# DAU_Kupplung_3phasig_V1_13.net
KiCad netlist of a schematic drawn in Altium Designer
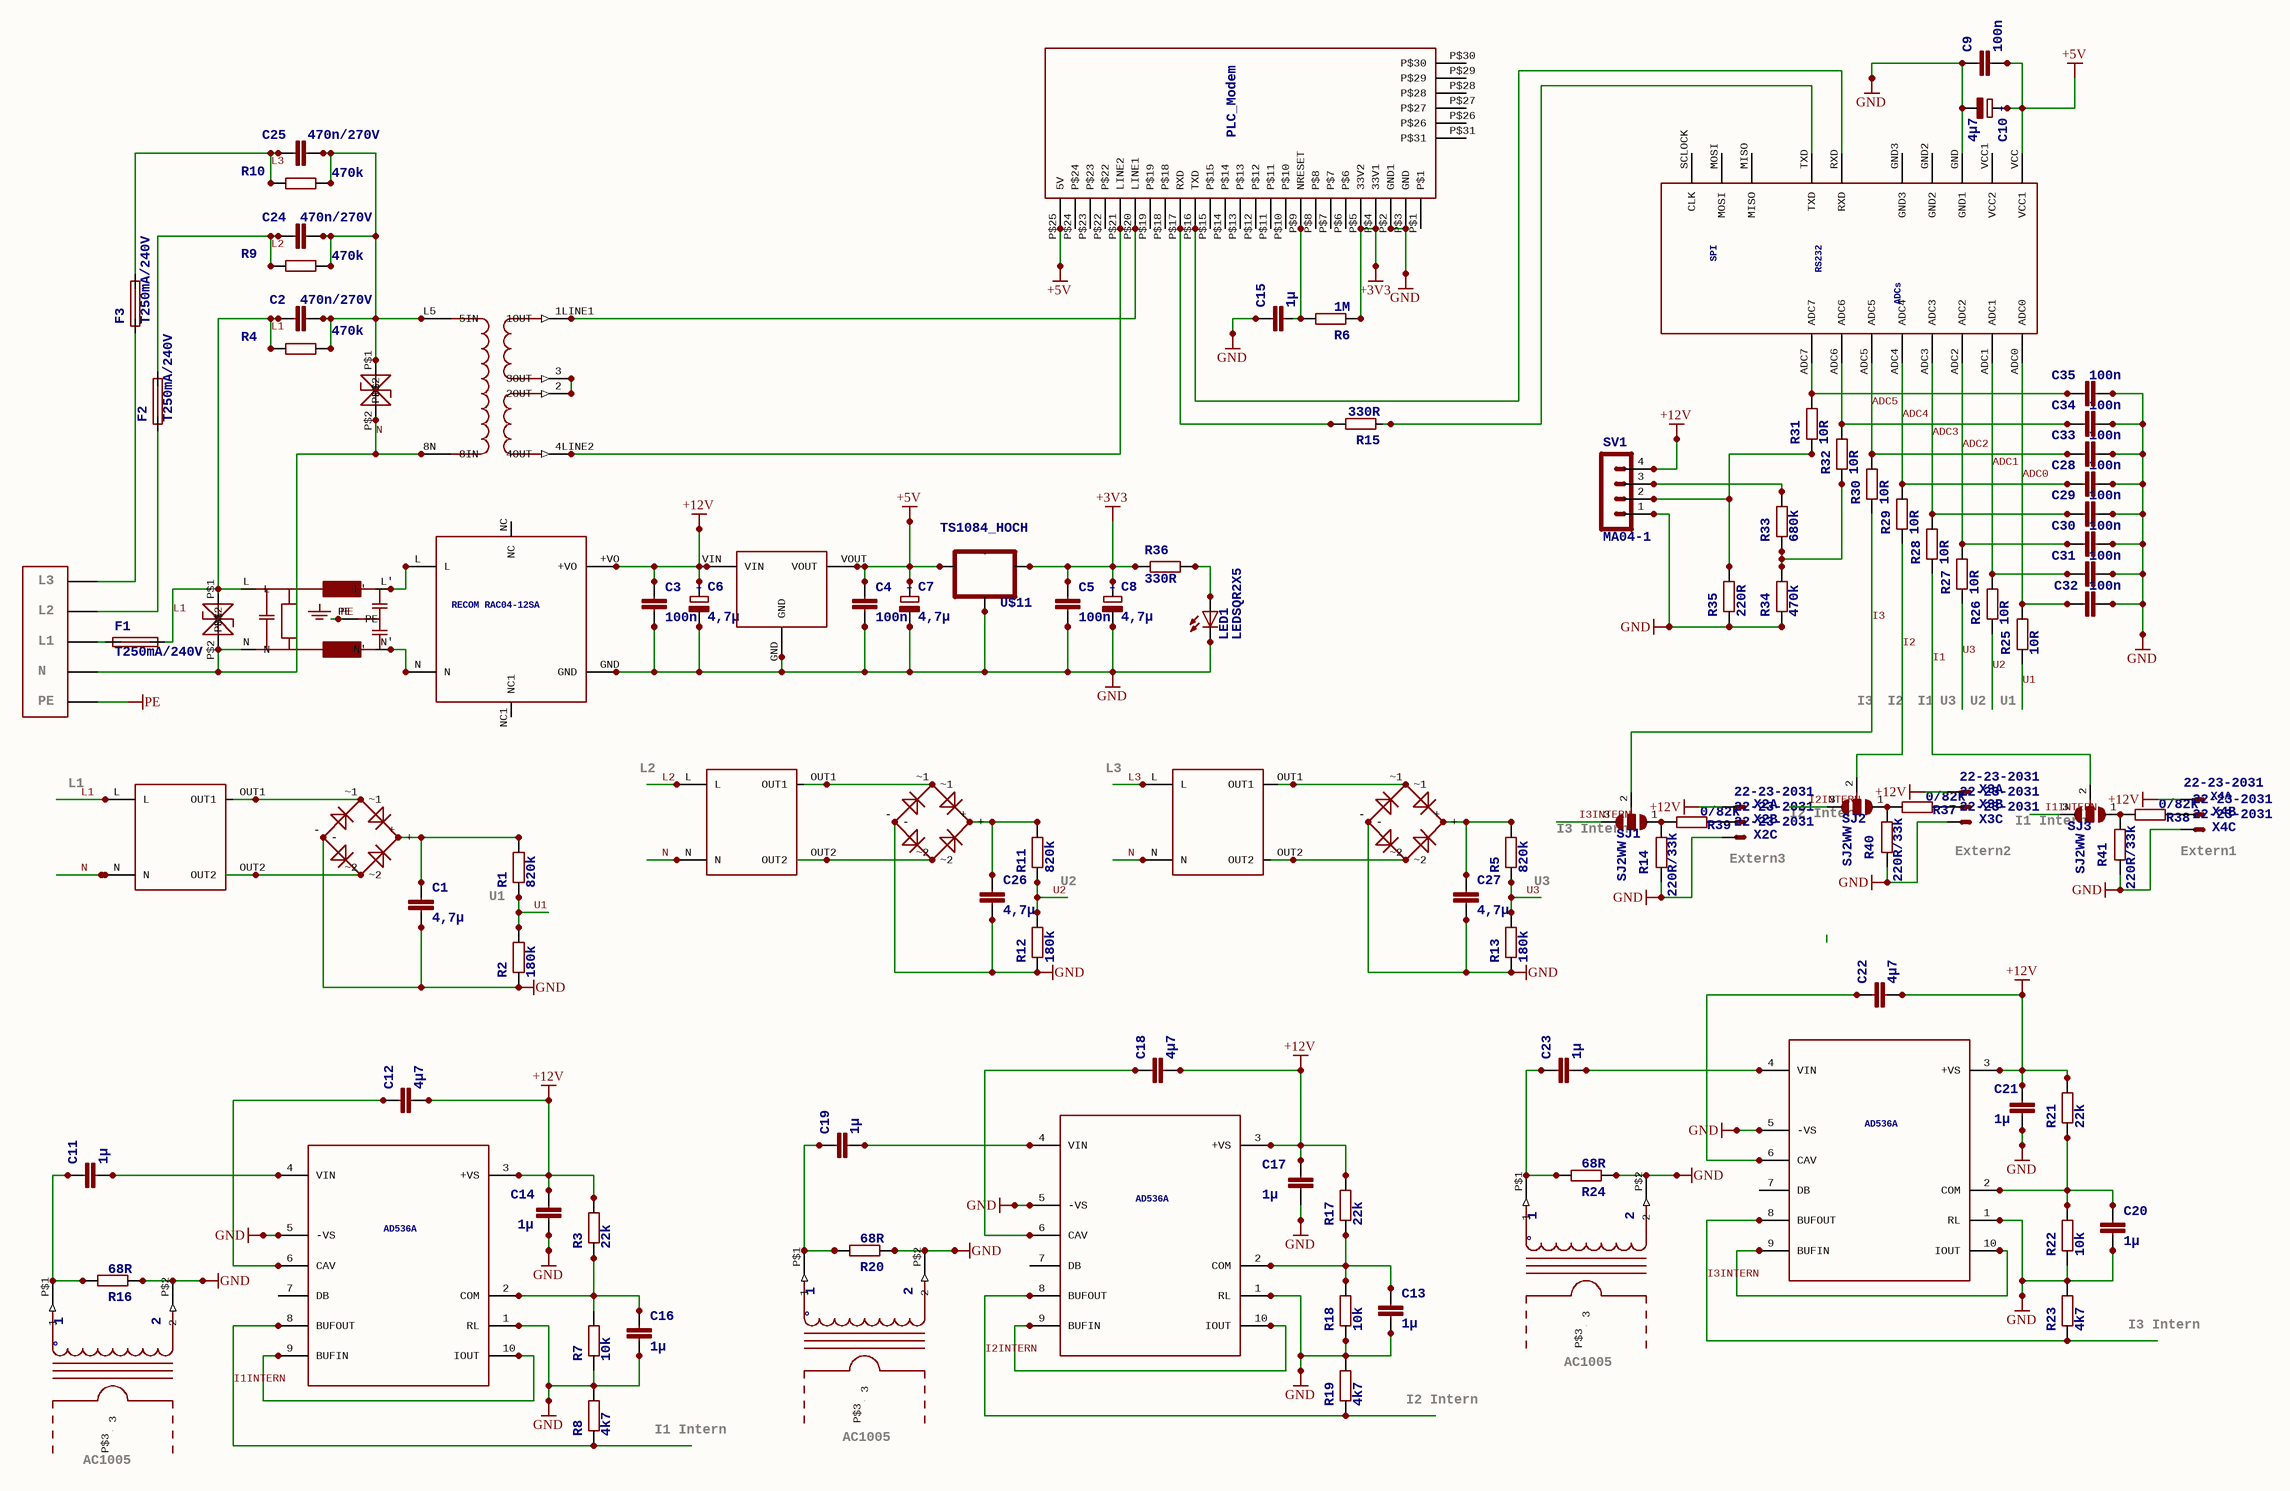
[diagram p0: DAU_Kupplung_3phasig_V1_13.SchDoc]

(export (version "E")
  (design (tool "Eeschema 10.0.6"))
  (components
    (comp (ref "AC1002_1")
      (value "AC1010")
      (footprint "AC1010")
      (fields (field (name "°") "°") (field (name "1") "1") (field (name "2") "2"))
      (libsource (lib "ADS") (part "AC1010"))
    )
    (comp (ref "C1")
      (value "4,7µ")
      (footprint "C1206")
      (description "<B>CAPACITOR</B>, European symbol")
      (libsource (lib "resistor") (part "C-EUC1206"))
    )
    (comp (ref "C2")
      (value "470n/270V")
      (footprint "C225-087X268")
      (description "<B>CAPACITOR</B>, European symbol")
      (libsource (lib "resistor") (part "C-EU225-087X268"))
    )
    (comp (ref "C3")
      (value "100n")
      (footprint "C0805K")
      (description "<B>CAPACITOR</B>, European symbol")
      (libsource (lib "") (part "C-EUC0805K_1"))
    )
    (comp (ref "C4")
      (value "100n")
      (footprint "C0805K")
      (description "<B>CAPACITOR</B>, European symbol")
      (libsource (lib "") (part "C-EUC0805K_1"))
    )
    (comp (ref "C5")
      (value "100n")
      (footprint "C0805K")
      (description "<B>CAPACITOR</B>, European symbol")
      (libsource (lib "") (part "C-EUC0805K_1"))
    )
    (comp (ref "C6")
      (value "4,7µ")
      (footprint "E2,5-6")
      (description "<B>POLARIZED CAPACITOR</B>, European symbol")
      (fields (field (name "+") "+"))
      (libsource (lib "resistor") (part "CPOL-EUE2.5-6"))
    )
    (comp (ref "C7")
      (value "4,7µ")
      (footprint "E2,5-6")
      (description "<B>POLARIZED CAPACITOR</B>, European symbol")
      (fields (field (name "+") "+"))
      (libsource (lib "resistor") (part "CPOL-EUE2.5-6"))
    )
    (comp (ref "C8")
      (value "4,7µ")
      (footprint "E2,5-6")
      (description "<B>POLARIZED CAPACITOR</B>, European symbol")
      (fields (field (name "+") "+"))
      (libsource (lib "resistor") (part "CPOL-EUE2.5-6"))
    )
    (comp (ref "C9")
      (value "100n")
      (footprint "C0805K")
      (description "<B>CAPACITOR</B>, European symbol")
      (libsource (lib "resistor") (part "C-EUC0805K"))
    )
    (comp (ref "C10")
      (value "4µ7")
      (footprint "E2,5-6E")
      (description "<B>POLARIZED CAPACITOR</B>, European symbol")
      (fields (field (name "+") "+"))
      (libsource (lib "rcl") (part "CPOL-EUE2,5-6E"))
    )
    (comp (ref "C11")
      (value "1µ")
      (footprint "C0805K")
      (description "<B>CAPACITOR</B>, European symbol")
      (libsource (lib "resistor") (part "C-EUC0805K"))
    )
    (comp (ref "C12")
      (value "4µ7")
      (footprint "C0805K")
      (description "<B>CAPACITOR</B>, European symbol")
      (libsource (lib "resistor") (part "C-EUC0805K"))
    )
    (comp (ref "C13")
      (value "1µ")
      (footprint "C0805K")
      (description "<B>CAPACITOR</B>, European symbol")
      (libsource (lib "") (part "C-EUC0805K_1"))
    )
    (comp (ref "C14")
      (value "1µ")
      (footprint "C0805K")
      (description "<B>CAPACITOR</B>, European symbol")
      (libsource (lib "") (part "C-EUC0805K_2"))
    )
    (comp (ref "C15")
      (value "1µ")
      (footprint "C0805K")
      (description "<B>CAPACITOR</B>, European symbol")
      (libsource (lib "resistor") (part "C-EUC0805K"))
    )
    (comp (ref "C16")
      (value "1µ")
      (footprint "C0805K")
      (description "<B>CAPACITOR</B>, European symbol")
      (libsource (lib "") (part "C-EUC0805K_1"))
    )
    (comp (ref "C17")
      (value "1µ")
      (footprint "C0805K")
      (description "<B>CAPACITOR</B>, European symbol")
      (libsource (lib "") (part "C-EUC0805K_2"))
    )
    (comp (ref "C18")
      (value "4µ7")
      (footprint "C0805K")
      (description "<B>CAPACITOR</B>, European symbol")
      (libsource (lib "resistor") (part "C-EUC0805K"))
    )
    (comp (ref "C19")
      (value "1µ")
      (footprint "C0805K")
      (description "<B>CAPACITOR</B>, European symbol")
      (libsource (lib "resistor") (part "C-EUC0805K"))
    )
    (comp (ref "C20")
      (value "1µ")
      (footprint "C0805K")
      (description "<B>CAPACITOR</B>, European symbol")
      (libsource (lib "") (part "C-EUC0805K_1"))
    )
    (comp (ref "C21")
      (value "1µ")
      (footprint "C0805K")
      (description "<B>CAPACITOR</B>, European symbol")
      (libsource (lib "") (part "C-EUC0805K_1"))
    )
    (comp (ref "C22")
      (value "4µ7")
      (footprint "C0805K")
      (description "<B>CAPACITOR</B>, European symbol")
      (libsource (lib "resistor") (part "C-EUC0805K"))
    )
    (comp (ref "C23")
      (value "1µ")
      (footprint "C0805K")
      (description "<B>CAPACITOR</B>, European symbol")
      (libsource (lib "resistor") (part "C-EUC0805K"))
    )
    (comp (ref "C24")
      (value "470n/270V")
      (footprint "C225-087X268")
      (description "<B>CAPACITOR</B>, European symbol")
      (libsource (lib "resistor") (part "C-EU225-087X268"))
    )
    (comp (ref "C25")
      (value "470n/270V")
      (footprint "C225-087X268")
      (description "<B>CAPACITOR</B>, European symbol")
      (libsource (lib "resistor") (part "C-EU225-087X268"))
    )
    (comp (ref "C26")
      (value "4,7µ")
      (footprint "C1206")
      (description "<B>CAPACITOR</B>, European symbol")
      (libsource (lib "resistor") (part "C-EUC1206"))
    )
    (comp (ref "C27")
      (value "4,7µ")
      (footprint "C1206")
      (description "<B>CAPACITOR</B>, European symbol")
      (libsource (lib "resistor") (part "C-EUC1206"))
    )
    (comp (ref "C28")
      (value "100n")
      (footprint "C0805K")
      (description "<B>CAPACITOR</B>, European symbol")
      (libsource (lib "resistor") (part "C-EUC0805K"))
    )
    (comp (ref "C29")
      (value "100n")
      (footprint "C0805K")
      (description "<B>CAPACITOR</B>, European symbol")
      (libsource (lib "resistor") (part "C-EUC0805K"))
    )
    (comp (ref "C30")
      (value "100n")
      (footprint "C0805K")
      (description "<B>CAPACITOR</B>, European symbol")
      (libsource (lib "resistor") (part "C-EUC0805K"))
    )
    (comp (ref "C31")
      (value "100n")
      (footprint "C0805K")
      (description "<B>CAPACITOR</B>, European symbol")
      (libsource (lib "resistor") (part "C-EUC0805K"))
    )
    (comp (ref "C32")
      (value "100n")
      (footprint "C0805K")
      (description "<B>CAPACITOR</B>, European symbol")
      (libsource (lib "resistor") (part "C-EUC0805K"))
    )
    (comp (ref "C33")
      (value "100n")
      (footprint "C0805K")
      (description "<B>CAPACITOR</B>, European symbol")
      (libsource (lib "resistor") (part "C-EUC0805K"))
    )
    (comp (ref "C34")
      (value "100n")
      (footprint "C0805K")
      (description "<B>CAPACITOR</B>, European symbol")
      (libsource (lib "resistor") (part "C-EUC0805K"))
    )
    (comp (ref "C35")
      (value "100n")
      (footprint "C0805K")
      (description "<B>CAPACITOR</B>, European symbol")
      (libsource (lib "resistor") (part "C-EUC0805K"))
    )
    (comp (ref "F1")
      (value "T250mA/240V")
      (footprint "TR5")
      (description "<b>FUSE</b><p>\nWickmann")
      (libsource (lib "fuse") (part "TR5"))
    )
    (comp (ref "F2")
      (value "T250mA/240V")
      (footprint "TR5")
      (description "<b>FUSE</b><p>\nWickmann")
      (libsource (lib "fuse") (part "TR5"))
    )
    (comp (ref "F3")
      (value "T250mA/240V")
      (footprint "TR5")
      (description "<b>FUSE</b><p>\nWickmann")
      (libsource (lib "fuse") (part "TR5"))
    )
    (comp (ref "LED1") (value "LEDSQR2X5") (footprint "LED2X5") (libsource (lib "led") (part "LEDSQR2X5")))
    (comp (ref "P6KE300CA") (value "P6KE300CA") (footprint "TSV") (libsource (lib "ADS") (part "TSV")))
    (comp (ref "R1")
      (value "820k")
      (footprint "R0805")
      (description "<B>RESISTOR</B>, European symbol")
      (libsource (lib "resistor") (part "R-EU_R0805"))
    )
    (comp (ref "R2")
      (value "180k")
      (footprint "R0805")
      (description "<B>RESISTOR</B>, European symbol")
      (libsource (lib "resistor") (part "R-EU_R0805"))
    )
    (comp (ref "R3")
      (value "22k")
      (footprint "R0805")
      (description "<B>RESISTOR</B>, European symbol")
      (libsource (lib "resistor") (part "R-EU_R0805"))
    )
    (comp (ref "R4")
      (value "470k")
      (footprint "0204/7")
      (description "<B>RESISTOR</B>, European symbol")
      (libsource (lib "resistor") (part "R-EU_0204/7"))
    )
    (comp (ref "R5")
      (value "820k")
      (footprint "R0805")
      (description "<B>RESISTOR</B>, European symbol")
      (libsource (lib "resistor") (part "R-EU_R0805"))
    )
    (comp (ref "R6")
      (value "1M")
      (footprint "R0805")
      (description "<B>RESISTOR</B>, European symbol")
      (libsource (lib "resistor") (part "R-EU_R0805"))
    )
    (comp (ref "R7")
      (value "10k")
      (footprint "R0805")
      (description "<B>RESISTOR</B>, European symbol")
      (libsource (lib "resistor") (part "R-EU_R0805"))
    )
    (comp (ref "R8")
      (value "4k7")
      (footprint "R0805")
      (description "<B>RESISTOR</B>, European symbol")
      (libsource (lib "resistor") (part "R-EU_R0805"))
    )
    (comp (ref "R9")
      (value "470k")
      (footprint "0204/7")
      (description "<B>RESISTOR</B>, European symbol")
      (libsource (lib "resistor") (part "R-EU_0204/7"))
    )
    (comp (ref "R10")
      (value "470k")
      (footprint "0204/7")
      (description "<B>RESISTOR</B>, European symbol")
      (libsource (lib "resistor") (part "R-EU_0204/7"))
    )
    (comp (ref "R11")
      (value "820k")
      (footprint "R0805")
      (description "<B>RESISTOR</B>, European symbol")
      (libsource (lib "resistor") (part "R-EU_R0805"))
    )
    (comp (ref "R12")
      (value "180k")
      (footprint "R0805")
      (description "<B>RESISTOR</B>, European symbol")
      (libsource (lib "resistor") (part "R-EU_R0805"))
    )
    (comp (ref "R13")
      (value "180k")
      (footprint "R0805")
      (description "<B>RESISTOR</B>, European symbol")
      (libsource (lib "resistor") (part "R-EU_R0805"))
    )
    (comp (ref "R14")
      (value "220R/33k")
      (footprint "R0805")
      (description "<B>RESISTOR</B>, European symbol")
      (libsource (lib "resistor") (part "R-EU_R0805"))
    )
    (comp (ref "R15")
      (value "330R")
      (footprint "R0805")
      (description "<B>RESISTOR</B>, European symbol")
      (libsource (lib "resistor") (part "R-EU_R0805"))
    )
    (comp (ref "R16")
      (value "68R")
      (footprint "0204/7")
      (description "<B>RESISTOR</B>, European symbol")
      (libsource (lib "resistor") (part "R-EU_0204/7"))
    )
    (comp (ref "R17")
      (value "22k")
      (footprint "R0805")
      (description "<B>RESISTOR</B>, European symbol")
      (libsource (lib "resistor") (part "R-EU_R0805"))
    )
    (comp (ref "R18")
      (value "10k")
      (footprint "R0805")
      (description "<B>RESISTOR</B>, European symbol")
      (libsource (lib "resistor") (part "R-EU_R0805"))
    )
    (comp (ref "R19")
      (value "4k7")
      (footprint "R0805")
      (description "<B>RESISTOR</B>, European symbol")
      (libsource (lib "resistor") (part "R-EU_R0805"))
    )
    (comp (ref "R20")
      (value "68R")
      (footprint "0204/7")
      (description "<B>RESISTOR</B>, European symbol")
      (libsource (lib "resistor") (part "R-EU_0204/7"))
    )
    (comp (ref "R21")
      (value "22k")
      (footprint "R0805")
      (description "<B>RESISTOR</B>, European symbol")
      (libsource (lib "resistor") (part "R-EU_R0805"))
    )
    (comp (ref "R22")
      (value "10k")
      (footprint "R0805")
      (description "<B>RESISTOR</B>, European symbol")
      (libsource (lib "resistor") (part "R-EU_R0805"))
    )
    (comp (ref "R23")
      (value "4k7")
      (footprint "R0805")
      (description "<B>RESISTOR</B>, European symbol")
      (libsource (lib "resistor") (part "R-EU_R0805"))
    )
    (comp (ref "R24")
      (value "68R")
      (footprint "0204/7")
      (description "<B>RESISTOR</B>, European symbol")
      (libsource (lib "resistor") (part "R-EU_0204/7"))
    )
    (comp (ref "R25")
      (value "10R")
      (footprint "R0805")
      (description "<B>RESISTOR</B>, European symbol")
      (libsource (lib "resistor") (part "R-EU_R0805"))
    )
    (comp (ref "R26")
      (value "10R")
      (footprint "R0805")
      (description "<B>RESISTOR</B>, European symbol")
      (libsource (lib "resistor") (part "R-EU_R0805"))
    )
    (comp (ref "R27")
      (value "10R")
      (footprint "R0805")
      (description "<B>RESISTOR</B>, European symbol")
      (libsource (lib "resistor") (part "R-EU_R0805"))
    )
    (comp (ref "R28")
      (value "10R")
      (footprint "R0805")
      (description "<B>RESISTOR</B>, European symbol")
      (libsource (lib "resistor") (part "R-EU_R0805"))
    )
    (comp (ref "R29")
      (value "10R")
      (footprint "R0805")
      (description "<B>RESISTOR</B>, European symbol")
      (libsource (lib "resistor") (part "R-EU_R0805"))
    )
    (comp (ref "R30")
      (value "10R")
      (footprint "R0805")
      (description "<B>RESISTOR</B>, European symbol")
      (libsource (lib "resistor") (part "R-EU_R0805"))
    )
    (comp (ref "R31")
      (value "10R")
      (footprint "R0805")
      (description "<B>RESISTOR</B>, European symbol")
      (libsource (lib "resistor") (part "R-EU_R0805"))
    )
    (comp (ref "R32")
      (value "10R")
      (footprint "R0805")
      (description "<B>RESISTOR</B>, European symbol")
      (libsource (lib "resistor") (part "R-EU_R0805"))
    )
    (comp (ref "R33")
      (value "680k")
      (footprint "R0805")
      (description "<B>RESISTOR</B>, European symbol")
      (libsource (lib "resistor") (part "R-EU_R0805"))
    )
    (comp (ref "R34")
      (value "470k")
      (footprint "R0805")
      (description "<B>RESISTOR</B>, European symbol")
      (libsource (lib "resistor") (part "R-EU_R0805"))
    )
    (comp (ref "R35")
      (value "220R")
      (footprint "R0805")
      (description "<B>RESISTOR</B>, European symbol")
      (libsource (lib "resistor") (part "R-EU_R0805"))
    )
    (comp (ref "R36")
      (value "330R")
      (footprint "R0805")
      (description "<B>RESISTOR</B>, European symbol")
      (libsource (lib "resistor") (part "R-EU_R0805"))
    )
    (comp (ref "R37")
      (value "0/82k")
      (footprint "R0805")
      (description "<B>RESISTOR</B>, European symbol")
      (libsource (lib "resistor") (part "R-EU_R0805"))
    )
    (comp (ref "R38")
      (value "0/82k")
      (footprint "R0805")
      (description "<B>RESISTOR</B>, European symbol")
      (libsource (lib "resistor") (part "R-EU_R0805"))
    )
    (comp (ref "R39")
      (value "0/82k")
      (footprint "R0805")
      (description "<B>RESISTOR</B>, European symbol")
      (libsource (lib "resistor") (part "R-EU_R0805"))
    )
    (comp (ref "R40")
      (value "220R/33k")
      (footprint "R0805")
      (description "<B>RESISTOR</B>, European symbol")
      (libsource (lib "resistor") (part "R-EU_R0805"))
    )
    (comp (ref "R41")
      (value "220R/33k")
      (footprint "R0805")
      (description "<B>RESISTOR</B>, European symbol")
      (libsource (lib "resistor") (part "R-EU_R0805"))
    )
    (comp (ref "SJ1")
      (value "SJ2WW")
      (footprint "SJ_2W")
      (description "SMD solder <b>JUMPER</b>")
      (libsource (lib "jumper") (part "SJ2WW"))
    )
    (comp (ref "SJ2")
      (value "SJ2WW")
      (footprint "SJ_2W")
      (description "SMD solder <b>JUMPER</b>")
      (libsource (lib "jumper") (part "SJ2WW"))
    )
    (comp (ref "SJ3")
      (value "SJ2WW")
      (footprint "SJ_2W")
      (description "SMD solder <b>JUMPER</b>")
      (libsource (lib "jumper") (part "SJ2WW"))
    )
    (comp (ref "SV1")
      (value "MA04-1")
      (footprint "MA04-1")
      (description "<b>PIN HEADER</b>")
      (libsource (lib "con-lstb") (part "MA04-1"))
    )
    (comp (ref "TSV2") (value "TSV") (footprint "TSV") (libsource (lib "ADS") (part "TSV")))
    (comp (ref "U$1")
      (value "RECOM_RAC04_12SA")
      (footprint "RAC04_12SA")
      (fields (field (name "RECOM RAC04-12SA") "RECOM RAC04-12SA"))
      (libsource (lib "ADS") (part "RECOM_RAC04_12SA"))
    )
    (comp (ref "U$2")
      (value "SICHERHEITSTRAFO")
      (footprint "TRAFO_0,35VA")
      (libsource (lib "ADS") (part "SICHERHEITSTRAFO"))
    )
    (comp (ref "U$3")
      (value "ADUC831_MINIMUM")
      (footprint "ADUC_MINIMUM")
      (fields (field (name "SPI") "SPI") (field (name "RS232") "RS232") (field (name "ADCS") "ADCs"))
      (libsource (lib "ADS_ADUCBoards") (part "ADUC831_MINIMUM"))
    )
    (comp (ref "U$4")
      (value "MODEMSTECKER")
      (footprint "MODEM_FUSS")
      (fields (field (name "PLC_MODEM") "PLC_Modem"))
      (libsource (lib "ADS") (part "MODEMSTECKER"))
    )
    (comp (ref "U$5")
      (value "PLC_UEBERTRAGER_V2")
      (footprint "PLC-UEBERTRAGER_V2")
      (libsource (lib "ADS1") (part "PLC_UEBERTRAGER_V2"))
    )
    (comp (ref "U$7")
      (value "AC1010")
      (footprint "AC1010")
      (fields (field (name "°") "°") (field (name "1") "1") (field (name "2") "2"))
      (libsource (lib "ADS") (part "AC1010"))
    )
    (comp (ref "U$8") (value "RECTIFIER") (footprint "RECTIFIER") (libsource (lib "ADS") (part "RECTIFIER")))
    (comp (ref "U$10")
      (value "RECOM_785_05")
      (footprint "RECOM785X")
      (libsource (lib "ADS") (part "RECOM_785_05"))
    )
    (comp (ref "U$11")
      (value "TS1084_HOCH")
      (footprint "TS1084_HOCH")
      (libsource (lib "ADS") (part "TS1084_HOCH"))
    )
    (comp (ref "U$12")
      (value "AD536")
      (footprint "TO100_10PIN")
      (fields (field (name "AD536A") "AD536A"))
      (libsource (lib "ADS") (part "AD536"))
    )
    (comp (ref "U$13")
      (value "AD536")
      (footprint "TO100_10PIN")
      (fields (field (name "AD536A") "AD536A"))
      (libsource (lib "ADS") (part "AD536"))
    )
    (comp (ref "U$14")
      (value "AC1010")
      (footprint "AC1010")
      (fields (field (name "°") "°") (field (name "1") "1") (field (name "2") "2"))
      (libsource (lib "ADS") (part "AC1010"))
    )
    (comp (ref "U$15")
      (value "AD536")
      (footprint "TO100_10PIN")
      (fields (field (name "AD536A") "AD536A"))
      (libsource (lib "ADS") (part "AD536"))
    )
    (comp (ref "U$16")
      (value "SICHERHEITSTRAFO")
      (footprint "TRAFO_0,35VA")
      (libsource (lib "ADS") (part "SICHERHEITSTRAFO"))
    )
    (comp (ref "U$17") (value "RECTIFIER") (footprint "RECTIFIER") (libsource (lib "ADS") (part "RECTIFIER")))
    (comp (ref "U$18")
      (value "SICHERHEITSTRAFO")
      (footprint "TRAFO_0,35VA")
      (libsource (lib "ADS") (part "SICHERHEITSTRAFO"))
    )
    (comp (ref "U$19") (value "RECTIFIER") (footprint "RECTIFIER") (libsource (lib "ADS") (part "RECTIFIER")))
    (comp (ref "U$20")
      (value "NETZFILTER_05_A")
      (footprint "NETZFILTER")
      (libsource (lib "ADS") (part "NETZFILTER_05_A"))
    )
    (comp (ref "X1")
      (value "CONNECTO_5_POL")
      (footprint "CONNECTOR_5_POL")
      (libsource (lib "ADS") (part "CONNECTO_5_POL"))
    )
    (comp (ref "X2")
      (value "22-23-2031")
      (footprint "22-23-2031")
      (description ".100\" (2.54mm) Center Header - 3 Pin")
      (fields (field (name "MF") "MOLEX"))
      (libsource (lib "con-molex") (part "22-23-2031"))
    )
    (comp (ref "X3")
      (value "22-23-2031")
      (footprint "22-23-2031")
      (description ".100\" (2.54mm) Center Header - 3 Pin")
      (fields (field (name "MF") "MOLEX"))
      (libsource (lib "con-molex") (part "22-23-2031"))
    )
    (comp (ref "X4")
      (value "22-23-2031")
      (footprint "22-23-2031")
      (description ".100\" (2.54mm) Center Header - 3 Pin")
      (fields (field (name "MF") "MOLEX"))
      (libsource (lib "con-molex") (part "22-23-2031"))
    )
  )
  (nets
    (net (code "1") (name "+3V3") (class "Default")
      (node (ref "C5") (pin "1") (pinfunction "1_1") (pintype "passive"))
      (node (ref "C8") (pin "+") (pinfunction "+_+") (pintype "passive"))
      (node (ref "R36") (pin "1") (pinfunction "1_1") (pintype "passive"))
      (node (ref "R6") (pin "1") (pinfunction "1_1") (pintype "passive"))
      (node (ref "U$11") (pin "OUT") (pinfunction "OUT_OUT") (pintype "passive"))
      (node (ref "U$4") (pin "P$4") (pinfunction "33V1_P$4") (pintype "passive"))
      (node (ref "U$4") (pin "P$5") (pinfunction "33V2_P$5") (pintype "passive"))
    )
    (net (code "2") (name "+5V") (class "Default")
      (node (ref "C10") (pin "+") (pinfunction "+_+") (pintype "passive"))
      (node (ref "C4") (pin "1") (pinfunction "1_1") (pintype "passive"))
      (node (ref "C7") (pin "+") (pinfunction "+_+") (pintype "passive"))
      (node (ref "C9") (pin "2") (pinfunction "2_2") (pintype "passive"))
      (node (ref "U$10") (pin "VOUT") (pinfunction "VOUT_VOUT") (pintype "passive"))
      (node (ref "U$11") (pin "IN") (pinfunction "IN_IN") (pintype "passive"))
      (node (ref "U$3") (pin "VCC") (pinfunction "VCC1_VCC") (pintype "passive"))
      (node (ref "U$4") (pin "P$25") (pinfunction "5V_P$25") (pintype "passive"))
    )
    (net (code "3") (name "+12V") (class "Default")
      (node (ref "C12") (pin "2") (pinfunction "2_2") (pintype "passive"))
      (node (ref "C14") (pin "2") (pinfunction "2_2") (pintype "passive"))
      (node (ref "C17") (pin "2") (pinfunction "2_2") (pintype "passive"))
      (node (ref "C18") (pin "2") (pinfunction "2_2") (pintype "passive"))
      (node (ref "C21") (pin "1") (pinfunction "1_1") (pintype "passive"))
      (node (ref "C22") (pin "2") (pinfunction "2_2") (pintype "passive"))
      (node (ref "C3") (pin "1") (pinfunction "1_1") (pintype "passive"))
      (node (ref "C6") (pin "+") (pinfunction "+_+") (pintype "passive"))
      (node (ref "R17") (pin "2") (pinfunction "2_2") (pintype "passive"))
      (node (ref "R21") (pin "2") (pinfunction "2_2") (pintype "passive"))
      (node (ref "R3") (pin "2") (pinfunction "2_2") (pintype "passive"))
      (node (ref "SV1") (pin "4") (pinfunction "4_4") (pintype "passive"))
      (node (ref "U$1") (pin "+VO") (pinfunction "+VO_+VO") (pintype "passive"))
      (node (ref "U$10") (pin "VIN") (pinfunction "VIN_VIN") (pintype "passive"))
      (node (ref "U$12") (pin "3") (pinfunction "+VS_3") (pintype "passive"))
      (node (ref "U$13") (pin "3") (pinfunction "+VS_3") (pintype "passive"))
      (node (ref "U$15") (pin "3") (pinfunction "+VS_3") (pintype "passive"))
      (node (ref "X2") (pin "1") (pinfunction "S_1") (pintype "passive"))
      (node (ref "X3") (pin "1") (pinfunction "S_1") (pintype "passive"))
      (node (ref "X4") (pin "1") (pinfunction "S_1") (pintype "passive"))
    )
    (net (code "4") (name "/ADC0") (class "Default")
      (node (ref "C32") (pin "1") (pinfunction "1_1") (pintype "passive"))
      (node (ref "R25") (pin "2") (pinfunction "2_2") (pintype "passive"))
      (node (ref "U$3") (pin "ADC0") (pinfunction "ADC0_ADC0") (pintype "passive"))
    )
    (net (code "5") (name "/ADC1") (class "Default")
      (node (ref "C31") (pin "1") (pinfunction "1_1") (pintype "passive"))
      (node (ref "R26") (pin "2") (pinfunction "2_2") (pintype "passive"))
      (node (ref "U$3") (pin "ADC1") (pinfunction "ADC1_ADC1") (pintype "passive"))
    )
    (net (code "6") (name "/ADC2") (class "Default")
      (node (ref "C30") (pin "1") (pinfunction "1_1") (pintype "passive"))
      (node (ref "R27") (pin "2") (pinfunction "2_2") (pintype "passive"))
      (node (ref "U$3") (pin "ADC2") (pinfunction "ADC2_ADC2") (pintype "passive"))
    )
    (net (code "7") (name "/ADC3") (class "Default")
      (node (ref "C29") (pin "1") (pinfunction "1_1") (pintype "passive"))
      (node (ref "R28") (pin "2") (pinfunction "2_2") (pintype "passive"))
      (node (ref "U$3") (pin "ADC3") (pinfunction "ADC3_ADC3") (pintype "passive"))
    )
    (net (code "8") (name "/ADC4") (class "Default")
      (node (ref "C28") (pin "1") (pinfunction "1_1") (pintype "passive"))
      (node (ref "R29") (pin "2") (pinfunction "2_2") (pintype "passive"))
      (node (ref "U$3") (pin "ADC4") (pinfunction "ADC4_ADC4") (pintype "passive"))
    )
    (net (code "9") (name "/ADC5") (class "Default")
      (node (ref "C33") (pin "1") (pinfunction "1_1") (pintype "passive"))
      (node (ref "R30") (pin "2") (pinfunction "2_2") (pintype "passive"))
      (node (ref "U$3") (pin "ADC5") (pinfunction "ADC5_ADC5") (pintype "passive"))
    )
    (net (code "10") (name "/I1") (class "Default")
      (node (ref "R28") (pin "1") (pinfunction "1_1") (pintype "passive"))
      (node (ref "SJ3") (pin "2") (pinfunction "2_2") (pintype "passive"))
    )
    (net (code "11") (name "/I1INTERN") (class "Default")
      (node (ref "R8") (pin "1") (pinfunction "1_1") (pintype "passive"))
      (node (ref "SJ3") (pin "3") (pinfunction "3_3") (pintype "passive"))
      (node (ref "U$13") (pin "8") (pinfunction "BUFOUT_8") (pintype "passive"))
    )
    (net (code "12") (name "/I2") (class "Default")
      (node (ref "R29") (pin "1") (pinfunction "1_1") (pintype "passive"))
      (node (ref "SJ2") (pin "2") (pinfunction "2_2") (pintype "passive"))
    )
    (net (code "13") (name "/I2INTERN") (class "Default")
      (node (ref "R19") (pin "1") (pinfunction "1_1") (pintype "passive"))
      (node (ref "SJ2") (pin "3") (pinfunction "3_3") (pintype "passive"))
      (node (ref "U$12") (pin "8") (pinfunction "BUFOUT_8") (pintype "passive"))
    )
    (net (code "14") (name "/I3") (class "Default")
      (node (ref "R30") (pin "1") (pinfunction "1_1") (pintype "passive"))
      (node (ref "SJ1") (pin "2") (pinfunction "2_2") (pintype "passive"))
    )
    (net (code "15") (name "/I3INTERN") (class "Default")
      (node (ref "R23") (pin "1") (pinfunction "1_1") (pintype "passive"))
      (node (ref "SJ1") (pin "3") (pinfunction "3_3") (pintype "passive"))
      (node (ref "U$15") (pin "8") (pinfunction "BUFOUT_8") (pintype "passive"))
    )
    (net (code "16") (name "/L1") (class "Default")
      (node (ref "C2") (pin "1") (pinfunction "1_1") (pintype "passive"))
      (node (ref "F1") (pin "2") (pinfunction "2_2") (pintype "passive"))
      (node (ref "P6KE300CA") (pin "P$1") (pinfunction "P$1_P$1") (pintype "passive"))
      (node (ref "R4") (pin "2") (pinfunction "2_2") (pintype "passive"))
      (node (ref "U$2") (pin "L") (pinfunction "L_L") (pintype "passive"))
      (node (ref "U$20") (pin "L") (pinfunction "L_L") (pintype "passive"))
    )
    (net (code "17") (name "/L2") (class "Default")
      (node (ref "C24") (pin "1") (pinfunction "1_1") (pintype "passive"))
      (node (ref "F2") (pin "2") (pinfunction "2_2") (pintype "passive"))
      (node (ref "R9") (pin "2") (pinfunction "2_2") (pintype "passive"))
      (node (ref "U$16") (pin "L") (pinfunction "L_L") (pintype "passive"))
    )
    (net (code "18") (name "/L3") (class "Default")
      (node (ref "C25") (pin "1") (pinfunction "1_1") (pintype "passive"))
      (node (ref "F3") (pin "2") (pinfunction "2_2") (pintype "passive"))
      (node (ref "R10") (pin "2") (pinfunction "2_2") (pintype "passive"))
      (node (ref "U$18") (pin "L") (pinfunction "L_L") (pintype "passive"))
    )
    (net (code "19") (name "/N") (class "Default")
      (node (ref "P6KE300CA") (pin "P$2") (pinfunction "P$2_P$2") (pintype "passive"))
      (node (ref "TSV2") (pin "P$2") (pinfunction "P$2_P$2") (pintype "passive"))
      (node (ref "U$16") (pin "N") (pinfunction "N_N") (pintype "passive"))
      (node (ref "U$18") (pin "N") (pinfunction "N_N") (pintype "passive"))
      (node (ref "U$2") (pin "N") (pinfunction "N_N") (pintype "passive"))
      (node (ref "U$20") (pin "N") (pinfunction "N_N") (pintype "passive"))
      (node (ref "U$5") (pin "8N") (pinfunction "8IN_8N") (pintype "passive"))
      (node (ref "X1") (pin "P$4") (pinfunction "P$4_P$4") (pintype "passive"))
    )
    (net (code "20") (name "/U1") (class "Default")
      (node (ref "R1") (pin "1") (pinfunction "1_1") (pintype "passive"))
      (node (ref "R2") (pin "2") (pinfunction "2_2") (pintype "passive"))
      (node (ref "R25") (pin "1") (pinfunction "1_1") (pintype "passive"))
    )
    (net (code "21") (name "/U2") (class "Default")
      (node (ref "R11") (pin "1") (pinfunction "1_1") (pintype "passive"))
      (node (ref "R12") (pin "2") (pinfunction "2_2") (pintype "passive"))
      (node (ref "R26") (pin "1") (pinfunction "1_1") (pintype "passive"))
    )
    (net (code "22") (name "/U3") (class "Default")
      (node (ref "R13") (pin "2") (pinfunction "2_2") (pintype "passive"))
      (node (ref "R27") (pin "1") (pinfunction "1_1") (pintype "passive"))
      (node (ref "R5") (pin "1") (pinfunction "1_1") (pintype "passive"))
    )
    (net (code "23") (name "GND") (class "Default")
      (node (ref "AC1002_1") (pin "P$2") (pinfunction "2_P$2") (pintype "output"))
      (node (ref "C1") (pin "2") (pinfunction "2_2") (pintype "passive"))
      (node (ref "C10") (pin "-") (pinfunction "-_-") (pintype "passive"))
      (node (ref "C13") (pin "2") (pinfunction "2_2") (pintype "passive"))
      (node (ref "C14") (pin "1") (pinfunction "1_1") (pintype "passive"))
      (node (ref "C15") (pin "1") (pinfunction "1_1") (pintype "passive"))
      (node (ref "C16") (pin "2") (pinfunction "2_2") (pintype "passive"))
      (node (ref "C17") (pin "1") (pinfunction "1_1") (pintype "passive"))
      (node (ref "C20") (pin "2") (pinfunction "2_2") (pintype "passive"))
      (node (ref "C21") (pin "2") (pinfunction "2_2") (pintype "passive"))
      (node (ref "C26") (pin "2") (pinfunction "2_2") (pintype "passive"))
      (node (ref "C27") (pin "2") (pinfunction "2_2") (pintype "passive"))
      (node (ref "C28") (pin "2") (pinfunction "2_2") (pintype "passive"))
      (node (ref "C29") (pin "2") (pinfunction "2_2") (pintype "passive"))
      (node (ref "C3") (pin "2") (pinfunction "2_2") (pintype "passive"))
      (node (ref "C30") (pin "2") (pinfunction "2_2") (pintype "passive"))
      (node (ref "C31") (pin "2") (pinfunction "2_2") (pintype "passive"))
      (node (ref "C32") (pin "2") (pinfunction "2_2") (pintype "passive"))
      (node (ref "C33") (pin "2") (pinfunction "2_2") (pintype "passive"))
      (node (ref "C34") (pin "2") (pinfunction "2_2") (pintype "passive"))
      (node (ref "C35") (pin "2") (pinfunction "2_2") (pintype "passive"))
      (node (ref "C4") (pin "2") (pinfunction "2_2") (pintype "passive"))
      (node (ref "C5") (pin "2") (pinfunction "2_2") (pintype "passive"))
      (node (ref "C6") (pin "-") (pinfunction "-_-") (pintype "passive"))
      (node (ref "C7") (pin "-") (pinfunction "-_-") (pintype "passive"))
      (node (ref "C8") (pin "-") (pinfunction "-_-") (pintype "passive"))
      (node (ref "C9") (pin "1") (pinfunction "1_1") (pintype "passive"))
      (node (ref "LED1") (pin "K") (pinfunction "C_K") (pintype "passive"))
      (node (ref "R12") (pin "1") (pinfunction "1_1") (pintype "passive"))
      (node (ref "R13") (pin "1") (pinfunction "1_1") (pintype "passive"))
      (node (ref "R14") (pin "1") (pinfunction "1_1") (pintype "passive"))
      (node (ref "R16") (pin "1") (pinfunction "1_1") (pintype "passive"))
      (node (ref "R18") (pin "1") (pinfunction "1_1") (pintype "passive"))
      (node (ref "R19") (pin "2") (pinfunction "2_2") (pintype "passive"))
      (node (ref "R2") (pin "1") (pinfunction "1_1") (pintype "passive"))
      (node (ref "R20") (pin "1") (pinfunction "1_1") (pintype "passive"))
      (node (ref "R22") (pin "1") (pinfunction "1_1") (pintype "passive"))
      (node (ref "R23") (pin "2") (pinfunction "2_2") (pintype "passive"))
      (node (ref "R24") (pin "1") (pinfunction "1_1") (pintype "passive"))
      (node (ref "R34") (pin "1") (pinfunction "1_1") (pintype "passive"))
      (node (ref "R35") (pin "1") (pinfunction "1_1") (pintype "passive"))
      (node (ref "R40") (pin "1") (pinfunction "1_1") (pintype "passive"))
      (node (ref "R41") (pin "1") (pinfunction "1_1") (pintype "passive"))
      (node (ref "R7") (pin "1") (pinfunction "1_1") (pintype "passive"))
      (node (ref "R8") (pin "2") (pinfunction "2_2") (pintype "passive"))
      (node (ref "SV1") (pin "1") (pinfunction "1_1") (pintype "passive"))
      (node (ref "U$1") (pin "GND") (pinfunction "GND_GND") (pintype "passive"))
      (node (ref "U$10") (pin "GND") (pinfunction "GND_GND") (pintype "passive"))
      (node (ref "U$11") (pin "GND") (pinfunction "GND_GND") (pintype "passive"))
      (node (ref "U$12") (pin "1") (pinfunction "RL_1") (pintype "passive"))
      (node (ref "U$12") (pin "5") (pinfunction "-VS_5") (pintype "passive"))
      (node (ref "U$13") (pin "1") (pinfunction "RL_1") (pintype "passive"))
      (node (ref "U$13") (pin "5") (pinfunction "-VS_5") (pintype "passive"))
      (node (ref "U$14") (pin "P$2") (pinfunction "2_P$2") (pintype "output"))
      (node (ref "U$15") (pin "1") (pinfunction "RL_1") (pintype "passive"))
      (node (ref "U$15") (pin "5") (pinfunction "-VS_5") (pintype "passive"))
      (node (ref "U$17") (pin "-") (pinfunction "-_-") (pintype "passive"))
      (node (ref "U$19") (pin "-") (pinfunction "-_-") (pintype "passive"))
      (node (ref "U$3") (pin "GND") (pinfunction "GND1_GND") (pintype "passive"))
      (node (ref "U$4") (pin "P$2") (pinfunction "GND1_P$2") (pintype "passive"))
      (node (ref "U$4") (pin "P$3") (pinfunction "GND_P$3") (pintype "passive"))
      (node (ref "U$7") (pin "P$2") (pinfunction "2_P$2") (pintype "output"))
      (node (ref "U$8") (pin "-") (pinfunction "-_-") (pintype "passive"))
      (node (ref "X2") (pin "3") (pinfunction "S_3") (pintype "passive"))
      (node (ref "X3") (pin "3") (pinfunction "S_3") (pintype "passive"))
      (node (ref "X4") (pin "3") (pinfunction "S_3") (pintype "passive"))
    )
    (net (code "24") (name "Net-(AC1002_1-1)") (class "Default")
      (node (ref "AC1002_1") (pin "P$1") (pinfunction "1_P$1") (pintype "output"))
      (node (ref "C11") (pin "1") (pinfunction "1_1") (pintype "passive"))
      (node (ref "R16") (pin "2") (pinfunction "2_2") (pintype "passive"))
    )
    (net (code "25") (name "Net-(C1-Pad1)") (class "Default")
      (node (ref "C1") (pin "1") (pinfunction "1_1") (pintype "passive"))
      (node (ref "R1") (pin "2") (pinfunction "2_2") (pintype "passive"))
      (node (ref "U$8") (pin "+") (pinfunction "+_+") (pintype "passive"))
    )
    (net (code "26") (name "Net-(C26-Pad1)") (class "Default")
      (node (ref "C26") (pin "1") (pinfunction "1_1") (pintype "passive"))
      (node (ref "R11") (pin "2") (pinfunction "2_2") (pintype "passive"))
      (node (ref "U$17") (pin "+") (pinfunction "+_+") (pintype "passive"))
    )
    (net (code "27") (name "Net-(C27-Pad1)") (class "Default")
      (node (ref "C27") (pin "1") (pinfunction "1_1") (pintype "passive"))
      (node (ref "R5") (pin "2") (pinfunction "2_2") (pintype "passive"))
      (node (ref "U$19") (pin "+") (pinfunction "+_+") (pintype "passive"))
    )
    (net (code "28") (name "Net-(C34-Pad1)") (class "Default")
      (node (ref "C34") (pin "1") (pinfunction "1_1") (pintype "passive"))
      (node (ref "R32") (pin "2") (pinfunction "2_2") (pintype "passive"))
      (node (ref "U$3") (pin "ADC6") (pinfunction "ADC6_ADC6") (pintype "passive"))
    )
    (net (code "29") (name "Net-(C35-Pad1)") (class "Default")
      (node (ref "C35") (pin "1") (pinfunction "1_1") (pintype "passive"))
      (node (ref "R31") (pin "2") (pinfunction "2_2") (pintype "passive"))
      (node (ref "U$3") (pin "ADC7") (pinfunction "ADC7_ADC7") (pintype "passive"))
    )
    (net (code "30") (name "Net-(F1-Pad1)") (class "Default")
      (node (ref "F1") (pin "1") (pinfunction "1_1") (pintype "passive"))
      (node (ref "X1") (pin "P$3") (pinfunction "P$3_P$3") (pintype "passive"))
    )
    (net (code "31") (name "Net-(F2-Pad1)") (class "Default")
      (node (ref "F2") (pin "1") (pinfunction "1_1") (pintype "passive"))
      (node (ref "X1") (pin "P$2") (pinfunction "P$2_P$2") (pintype "passive"))
    )
    (net (code "32") (name "Net-(F3-Pad1)") (class "Default")
      (node (ref "F3") (pin "1") (pinfunction "1_1") (pintype "passive"))
      (node (ref "X1") (pin "P$1") (pinfunction "P$1_P$1") (pintype "passive"))
    )
    (net (code "33") (name "Net-(LED1-PadA)") (class "Default")
      (node (ref "LED1") (pin "A") (pinfunction "A_A") (pintype "passive"))
      (node (ref "R36") (pin "2") (pinfunction "2_2") (pintype "passive"))
    )
    (net (code "34") (name "Net-(R14-Pad2)") (class "Default")
      (node (ref "R14") (pin "2") (pinfunction "2_2") (pintype "passive"))
      (node (ref "R39") (pin "2") (pinfunction "2_2") (pintype "passive"))
      (node (ref "SJ1") (pin "1") (pinfunction "1_1") (pintype "passive"))
    )
    (net (code "35") (name "Net-(R15-Pad1)") (class "Default")
      (node (ref "R15") (pin "1") (pinfunction "1_1") (pintype "passive"))
      (node (ref "U$3") (pin "TXD") (pinfunction "TXD_TXD") (pintype "passive"))
    )
    (net (code "36") (name "Net-(R31-Pad1)") (class "Default")
      (node (ref "R31") (pin "1") (pinfunction "1_1") (pintype "passive"))
      (node (ref "R35") (pin "2") (pinfunction "2_2") (pintype "passive"))
      (node (ref "SV1") (pin "2") (pinfunction "2_2") (pintype "passive"))
    )
    (net (code "37") (name "Net-(R32-Pad1)") (class "Default")
      (node (ref "R32") (pin "1") (pinfunction "1_1") (pintype "passive"))
      (node (ref "R33") (pin "1") (pinfunction "1_1") (pintype "passive"))
      (node (ref "R34") (pin "2") (pinfunction "2_2") (pintype "passive"))
    )
    (net (code "38") (name "Net-(R33-Pad2)") (class "Default")
      (node (ref "R33") (pin "2") (pinfunction "2_2") (pintype "passive"))
      (node (ref "SV1") (pin "3") (pinfunction "3_3") (pintype "passive"))
    )
    (net (code "39") (name "Net-(R37-Pad2)") (class "Default")
      (node (ref "R37") (pin "2") (pinfunction "2_2") (pintype "passive"))
      (node (ref "R40") (pin "2") (pinfunction "2_2") (pintype "passive"))
      (node (ref "SJ2") (pin "1") (pinfunction "1_1") (pintype "passive"))
    )
    (net (code "40") (name "Net-(R38-Pad2)") (class "Default")
      (node (ref "R38") (pin "2") (pinfunction "2_2") (pintype "passive"))
      (node (ref "R41") (pin "2") (pinfunction "2_2") (pintype "passive"))
      (node (ref "SJ3") (pin "1") (pinfunction "1_1") (pintype "passive"))
    )
    (net (code "41") (name "Net-(U$1-PadL)") (class "Default")
      (node (ref "U$1") (pin "L") (pinfunction "L_L") (pintype "passive"))
      (node (ref "U$20") (pin "L'") (pinfunction "L'_L'") (pintype "passive"))
    )
    (net (code "42") (name "Net-(U$1-PadN)") (class "Default")
      (node (ref "U$1") (pin "N") (pinfunction "N_N") (pintype "passive"))
      (node (ref "U$20") (pin "N'") (pinfunction "N'_N'") (pintype "passive"))
    )
    (net (code "43") (name "Net-(U$2-PadOUT1)") (class "Default")
      (node (ref "U$2") (pin "OUT1") (pinfunction "OUT1_OUT1") (pintype "passive"))
      (node (ref "U$8") (pin "~1") (pinfunction "~1_~1") (pintype "passive"))
    )
    (net (code "44") (name "Net-(U$2-PadOUT2)") (class "Default")
      (node (ref "U$2") (pin "OUT2") (pinfunction "OUT2_OUT2") (pintype "passive"))
      (node (ref "U$8") (pin "~2") (pinfunction "~2_~2") (pintype "passive"))
    )
    (net (code "45") (name "Net-(U$4-LINE1)") (class "Default")
      (node (ref "U$4") (pin "P$20") (pinfunction "LINE1_P$20") (pintype "passive"))
      (node (ref "U$5") (pin "1LINE1") (pinfunction "1OUT_1LINE1") (pintype "output"))
    )
    (net (code "46") (name "Net-(U$4-LINE2)") (class "Default")
      (node (ref "U$4") (pin "P$21") (pinfunction "LINE2_P$21") (pintype "passive"))
      (node (ref "U$5") (pin "4LINE2") (pinfunction "4OUT_4LINE2") (pintype "output"))
    )
    (net (code "47") (name "Net-(U$4-NRESET)") (class "Default")
      (node (ref "C15") (pin "2") (pinfunction "2_2") (pintype "passive"))
      (node (ref "R6") (pin "2") (pinfunction "2_2") (pintype "passive"))
      (node (ref "U$4") (pin "P$9") (pinfunction "NRESET_P$9") (pintype "passive"))
    )
    (net (code "48") (name "Net-(U$4-RXD)") (class "Default")
      (node (ref "R15") (pin "2") (pinfunction "2_2") (pintype "passive"))
      (node (ref "U$4") (pin "P$17") (pinfunction "RXD_P$17") (pintype "passive"))
    )
    (net (code "49") (name "Net-(U$4-TXD)") (class "Default")
      (node (ref "U$3") (pin "RXD") (pinfunction "RXD_RXD") (pintype "passive"))
      (node (ref "U$4") (pin "P$16") (pinfunction "TXD_P$16") (pintype "passive"))
    )
    (net (code "50") (name "Net-(U$5-2OUT)") (class "Default")
      (node (ref "U$5") (pin "2") (pinfunction "2OUT_2") (pintype "output"))
      (node (ref "U$5") (pin "3") (pinfunction "3OUT_3") (pintype "output"))
    )
    (net (code "51") (name "Net-(U$5-5IN)") (class "Default")
      (node (ref "C2") (pin "2") (pinfunction "2_2") (pintype "passive"))
      (node (ref "C24") (pin "2") (pinfunction "2_2") (pintype "passive"))
      (node (ref "C25") (pin "2") (pinfunction "2_2") (pintype "passive"))
      (node (ref "R10") (pin "1") (pinfunction "1_1") (pintype "passive"))
      (node (ref "R4") (pin "1") (pinfunction "1_1") (pintype "passive"))
      (node (ref "R9") (pin "1") (pinfunction "1_1") (pintype "passive"))
      (node (ref "TSV2") (pin "P$1") (pinfunction "P$1_P$1") (pintype "passive"))
      (node (ref "U$5") (pin "L5") (pinfunction "5IN_L5") (pintype "passive"))
    )
    (net (code "52") (name "Net-(U$7-1)") (class "Default")
      (node (ref "C19") (pin "1") (pinfunction "1_1") (pintype "passive"))
      (node (ref "R20") (pin "2") (pinfunction "2_2") (pintype "passive"))
      (node (ref "U$7") (pin "P$1") (pinfunction "1_P$1") (pintype "output"))
    )
    (net (code "53") (name "Net-(U$12-BUFIN)") (class "Default")
      (node (ref "U$12") (pin "10") (pinfunction "IOUT_10") (pintype "passive"))
      (node (ref "U$12") (pin "9") (pinfunction "BUFIN_9") (pintype "passive"))
    )
    (net (code "54") (name "Net-(U$12-CAV)") (class "Default")
      (node (ref "C18") (pin "1") (pinfunction "1_1") (pintype "passive"))
      (node (ref "U$12") (pin "6") (pinfunction "CAV_6") (pintype "passive"))
    )
    (net (code "55") (name "Net-(U$12-COM)") (class "Default")
      (node (ref "C13") (pin "1") (pinfunction "1_1") (pintype "passive"))
      (node (ref "R17") (pin "1") (pinfunction "1_1") (pintype "passive"))
      (node (ref "R18") (pin "2") (pinfunction "2_2") (pintype "passive"))
      (node (ref "U$12") (pin "2") (pinfunction "COM_2") (pintype "passive"))
    )
    (net (code "56") (name "Net-(U$12-VIN)") (class "Default")
      (node (ref "C19") (pin "2") (pinfunction "2_2") (pintype "passive"))
      (node (ref "U$12") (pin "4") (pinfunction "VIN_4") (pintype "passive"))
    )
    (net (code "57") (name "Net-(U$13-BUFIN)") (class "Default")
      (node (ref "U$13") (pin "10") (pinfunction "IOUT_10") (pintype "passive"))
      (node (ref "U$13") (pin "9") (pinfunction "BUFIN_9") (pintype "passive"))
    )
    (net (code "58") (name "Net-(U$13-CAV)") (class "Default")
      (node (ref "C12") (pin "1") (pinfunction "1_1") (pintype "passive"))
      (node (ref "U$13") (pin "6") (pinfunction "CAV_6") (pintype "passive"))
    )
    (net (code "59") (name "Net-(U$13-COM)") (class "Default")
      (node (ref "C16") (pin "1") (pinfunction "1_1") (pintype "passive"))
      (node (ref "R3") (pin "1") (pinfunction "1_1") (pintype "passive"))
      (node (ref "R7") (pin "2") (pinfunction "2_2") (pintype "passive"))
      (node (ref "U$13") (pin "2") (pinfunction "COM_2") (pintype "passive"))
    )
    (net (code "60") (name "Net-(U$13-VIN)") (class "Default")
      (node (ref "C11") (pin "2") (pinfunction "2_2") (pintype "passive"))
      (node (ref "U$13") (pin "4") (pinfunction "VIN_4") (pintype "passive"))
    )
    (net (code "61") (name "Net-(U$14-1)") (class "Default")
      (node (ref "C23") (pin "1") (pinfunction "1_1") (pintype "passive"))
      (node (ref "R24") (pin "2") (pinfunction "2_2") (pintype "passive"))
      (node (ref "U$14") (pin "P$1") (pinfunction "1_P$1") (pintype "output"))
    )
    (net (code "62") (name "Net-(U$15-BUFIN)") (class "Default")
      (node (ref "U$15") (pin "10") (pinfunction "IOUT_10") (pintype "passive"))
      (node (ref "U$15") (pin "9") (pinfunction "BUFIN_9") (pintype "passive"))
    )
    (net (code "63") (name "Net-(U$15-CAV)") (class "Default")
      (node (ref "C22") (pin "1") (pinfunction "1_1") (pintype "passive"))
      (node (ref "U$15") (pin "6") (pinfunction "CAV_6") (pintype "passive"))
    )
    (net (code "64") (name "Net-(U$15-COM)") (class "Default")
      (node (ref "C20") (pin "1") (pinfunction "1_1") (pintype "passive"))
      (node (ref "R21") (pin "1") (pinfunction "1_1") (pintype "passive"))
      (node (ref "R22") (pin "2") (pinfunction "2_2") (pintype "passive"))
      (node (ref "U$15") (pin "2") (pinfunction "COM_2") (pintype "passive"))
    )
    (net (code "65") (name "Net-(U$15-VIN)") (class "Default")
      (node (ref "C23") (pin "2") (pinfunction "2_2") (pintype "passive"))
      (node (ref "U$15") (pin "4") (pinfunction "VIN_4") (pintype "passive"))
    )
    (net (code "66") (name "Net-(U$16-PadOUT1)") (class "Default")
      (node (ref "U$16") (pin "OUT1") (pinfunction "OUT1_OUT1") (pintype "passive"))
      (node (ref "U$17") (pin "~1") (pinfunction "~1_~1") (pintype "passive"))
    )
    (net (code "67") (name "Net-(U$16-PadOUT2)") (class "Default")
      (node (ref "U$16") (pin "OUT2") (pinfunction "OUT2_OUT2") (pintype "passive"))
      (node (ref "U$17") (pin "~2") (pinfunction "~2_~2") (pintype "passive"))
    )
    (net (code "68") (name "Net-(U$18-PadOUT1)") (class "Default")
      (node (ref "U$18") (pin "OUT1") (pinfunction "OUT1_OUT1") (pintype "passive"))
      (node (ref "U$19") (pin "~1") (pinfunction "~1_~1") (pintype "passive"))
    )
    (net (code "69") (name "Net-(U$18-PadOUT2)") (class "Default")
      (node (ref "U$18") (pin "OUT2") (pinfunction "OUT2_OUT2") (pintype "passive"))
      (node (ref "U$19") (pin "~2") (pinfunction "~2_~2") (pintype "passive"))
    )
    (net (code "70") (name "Net-(X2B-S)") (class "Default")
      (node (ref "R39") (pin "1") (pinfunction "1_1") (pintype "passive"))
      (node (ref "X2") (pin "2") (pinfunction "S_2") (pintype "passive"))
    )
    (net (code "71") (name "Net-(X3B-S)") (class "Default")
      (node (ref "R37") (pin "1") (pinfunction "1_1") (pintype "passive"))
      (node (ref "X3") (pin "2") (pinfunction "S_2") (pintype "passive"))
    )
    (net (code "72") (name "Net-(X4B-S)") (class "Default")
      (node (ref "R38") (pin "1") (pinfunction "1_1") (pintype "passive"))
      (node (ref "X4") (pin "2") (pinfunction "S_2") (pintype "passive"))
    )
    (net (code "73") (name "PE") (class "Default")
      (node (ref "U$20") (pin "PE") (pinfunction "PE_PE") (pintype "passive"))
      (node (ref "X1") (pin "P$5") (pinfunction "P$5_P$5") (pintype "passive"))
    )
    (net (code "74") (name "unconnected-(AC1002_1-3-PadP$3)") (class "Default")
      (node (ref "AC1002_1") (pin "P$3") (pinfunction "3_P$3") (pintype "passive"))
    )
    (net (code "75") (name "unconnected-(U$1-PadNC)") (class "Default")
      (node (ref "U$1") (pin "NC") (pinfunction "NC_NC") (pintype "passive"))
    )
    (net (code "76") (name "unconnected-(U$1-PadNC1)") (class "Default")
      (node (ref "U$1") (pin "NC1") (pinfunction "NC1_NC1") (pintype "passive"))
    )
    (net (code "77") (name "unconnected-(U$3-CLK-PadSCLOCK)") (class "Default")
      (node (ref "U$3") (pin "SCLOCK") (pinfunction "CLK_SCLOCK") (pintype "passive"))
    )
    (net (code "78") (name "unconnected-(U$3-PadGND2)") (class "Default")
      (node (ref "U$3") (pin "GND2") (pinfunction "GND2_GND2") (pintype "passive"))
    )
    (net (code "79") (name "unconnected-(U$3-PadGND3)") (class "Default")
      (node (ref "U$3") (pin "GND3") (pinfunction "GND3_GND3") (pintype "passive"))
    )
    (net (code "80") (name "unconnected-(U$3-PadMISO)") (class "Default")
      (node (ref "U$3") (pin "MISO") (pinfunction "MISO_MISO") (pintype "passive"))
    )
    (net (code "81") (name "unconnected-(U$3-PadMOSI)") (class "Default")
      (node (ref "U$3") (pin "MOSI") (pinfunction "MOSI_MOSI") (pintype "passive"))
    )
    (net (code "82") (name "unconnected-(U$3-VCC2-PadVCC1)") (class "Default")
      (node (ref "U$3") (pin "VCC1") (pinfunction "VCC2_VCC1") (pintype "passive"))
    )
    (net (code "83") (name "unconnected-(U$4-PadP$1)") (class "Default")
      (node (ref "U$4") (pin "P$1") (pinfunction "P$1_P$1") (pintype "passive"))
    )
    (net (code "84") (name "unconnected-(U$4-PadP$6)") (class "Default")
      (node (ref "U$4") (pin "P$6") (pinfunction "P$6_P$6") (pintype "passive"))
    )
    (net (code "85") (name "unconnected-(U$4-PadP$7)") (class "Default")
      (node (ref "U$4") (pin "P$7") (pinfunction "P$7_P$7") (pintype "passive"))
    )
    (net (code "86") (name "unconnected-(U$4-PadP$8)") (class "Default")
      (node (ref "U$4") (pin "P$8") (pinfunction "P$8_P$8") (pintype "passive"))
    )
    (net (code "87") (name "unconnected-(U$4-PadP$10)") (class "Default")
      (node (ref "U$4") (pin "P$10") (pinfunction "P$10_P$10") (pintype "passive"))
    )
    (net (code "88") (name "unconnected-(U$4-PadP$11)") (class "Default")
      (node (ref "U$4") (pin "P$11") (pinfunction "P$11_P$11") (pintype "passive"))
    )
    (net (code "89") (name "unconnected-(U$4-PadP$12)") (class "Default")
      (node (ref "U$4") (pin "P$12") (pinfunction "P$12_P$12") (pintype "passive"))
    )
    (net (code "90") (name "unconnected-(U$4-PadP$13)") (class "Default")
      (node (ref "U$4") (pin "P$13") (pinfunction "P$13_P$13") (pintype "passive"))
    )
    (net (code "91") (name "unconnected-(U$4-PadP$14)") (class "Default")
      (node (ref "U$4") (pin "P$14") (pinfunction "P$14_P$14") (pintype "passive"))
    )
    (net (code "92") (name "unconnected-(U$4-PadP$15)") (class "Default")
      (node (ref "U$4") (pin "P$15") (pinfunction "P$15_P$15") (pintype "passive"))
    )
    (net (code "93") (name "unconnected-(U$4-PadP$18)") (class "Default")
      (node (ref "U$4") (pin "P$18") (pinfunction "P$18_P$18") (pintype "passive"))
    )
    (net (code "94") (name "unconnected-(U$4-PadP$19)") (class "Default")
      (node (ref "U$4") (pin "P$19") (pinfunction "P$19_P$19") (pintype "passive"))
    )
    (net (code "95") (name "unconnected-(U$4-PadP$22)") (class "Default")
      (node (ref "U$4") (pin "P$22") (pinfunction "P$22_P$22") (pintype "passive"))
    )
    (net (code "96") (name "unconnected-(U$4-PadP$23)") (class "Default")
      (node (ref "U$4") (pin "P$23") (pinfunction "P$23_P$23") (pintype "passive"))
    )
    (net (code "97") (name "unconnected-(U$4-PadP$24)") (class "Default")
      (node (ref "U$4") (pin "P$24") (pinfunction "P$24_P$24") (pintype "passive"))
    )
    (net (code "98") (name "unconnected-(U$4-PadP$26)") (class "Default")
      (node (ref "U$4") (pin "P$26") (pinfunction "P$26_P$26") (pintype "passive"))
    )
    (net (code "99") (name "unconnected-(U$4-PadP$27)") (class "Default")
      (node (ref "U$4") (pin "P$27") (pinfunction "P$27_P$27") (pintype "passive"))
    )
    (net (code "100") (name "unconnected-(U$4-PadP$28)") (class "Default")
      (node (ref "U$4") (pin "P$28") (pinfunction "P$28_P$28") (pintype "passive"))
    )
    (net (code "101") (name "unconnected-(U$4-PadP$29)") (class "Default")
      (node (ref "U$4") (pin "P$29") (pinfunction "P$29_P$29") (pintype "passive"))
    )
    (net (code "102") (name "unconnected-(U$4-PadP$30)") (class "Default")
      (node (ref "U$4") (pin "P$30") (pinfunction "P$30_P$30") (pintype "passive"))
    )
    (net (code "103") (name "unconnected-(U$4-PadP$31)") (class "Default")
      (node (ref "U$4") (pin "P$31") (pinfunction "P$31_P$31") (pintype "passive"))
    )
    (net (code "104") (name "unconnected-(U$7-3-PadP$3)") (class "Default")
      (node (ref "U$7") (pin "P$3") (pinfunction "3_P$3") (pintype "passive"))
    )
    (net (code "105") (name "unconnected-(U$12-DB-Pad7)") (class "Default")
      (node (ref "U$12") (pin "7") (pinfunction "DB_7") (pintype "passive"))
    )
    (net (code "106") (name "unconnected-(U$13-DB-Pad7)") (class "Default")
      (node (ref "U$13") (pin "7") (pinfunction "DB_7") (pintype "passive"))
    )
    (net (code "107") (name "unconnected-(U$14-3-PadP$3)") (class "Default")
      (node (ref "U$14") (pin "P$3") (pinfunction "3_P$3") (pintype "passive"))
    )
    (net (code "108") (name "unconnected-(U$15-DB-Pad7)") (class "Default")
      (node (ref "U$15") (pin "7") (pinfunction "DB_7") (pintype "passive"))
    )
  )
)
